# ui_ext_conn.net
KiCad netlist of a schematic drawn in Altium Designer
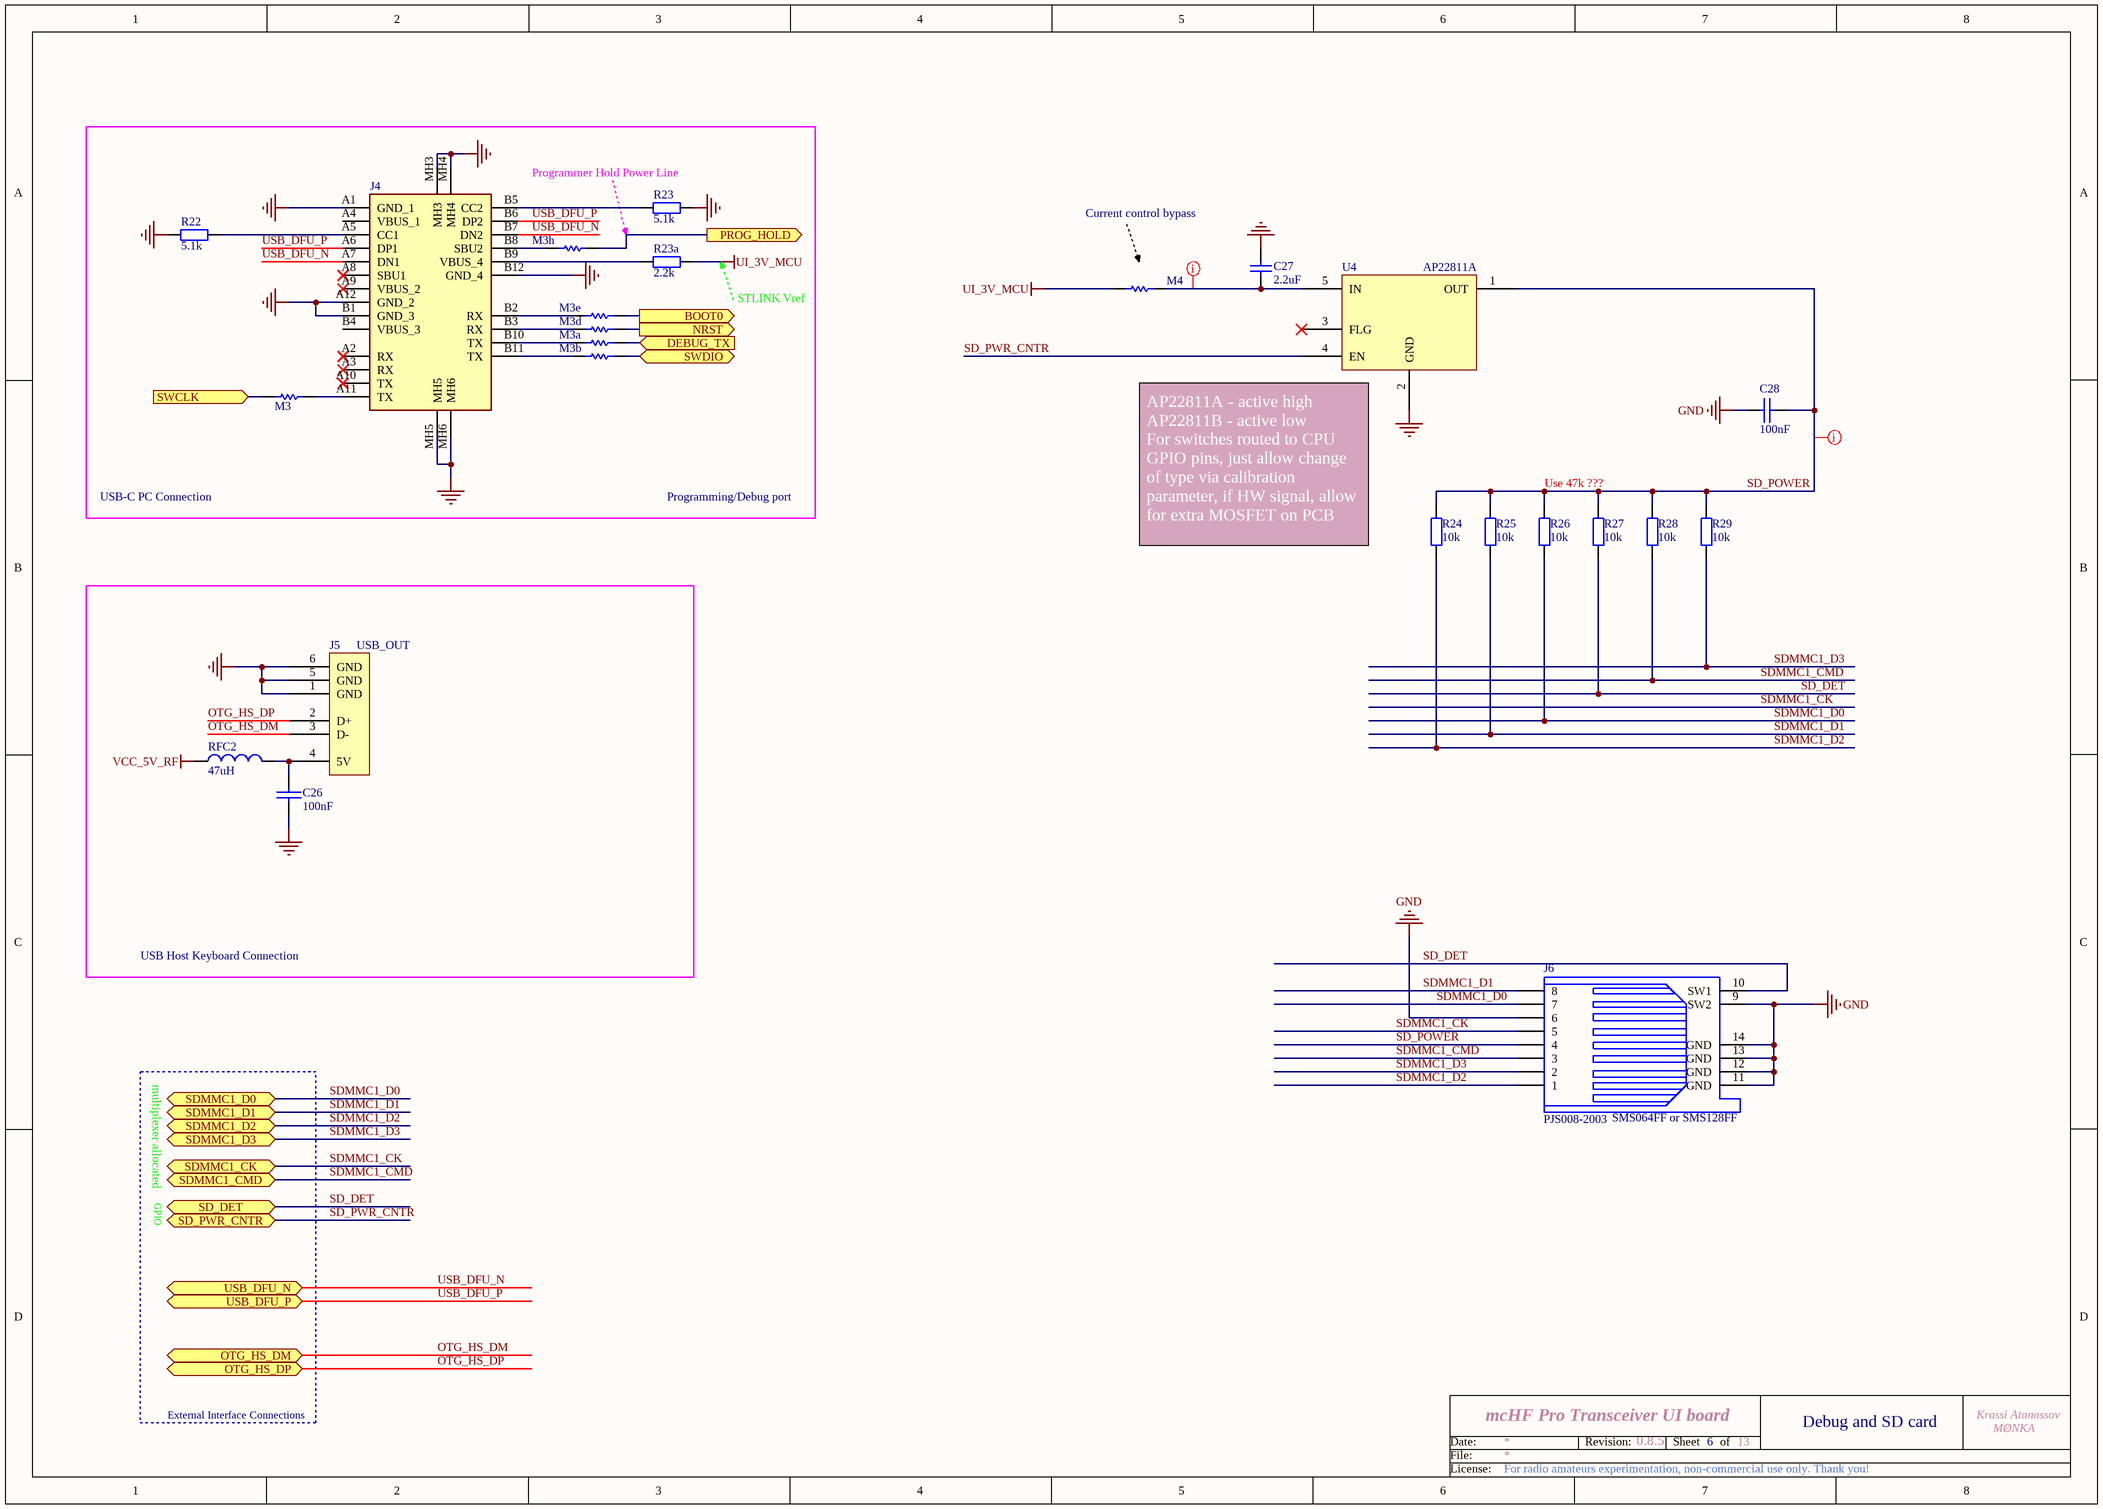
[diagram p0: ui_ext_conn.SchDoc]

(export (version "E")
  (design (tool "Eeschema 10.0.6"))
  (components
    (comp (ref "C26")
      (value "100nF")
      (footprint "0805")
      (description "Capacitor")
      (libsource (lib "mcHF_ui") (part "CAP"))
    )
    (comp (ref "C27")
      (value "2.2uF")
      (footprint "0805")
      (description "0603  X5R 1礔")
      (fields (field (name "TOLERANCE") "10%"))
      (libsource (lib "MB963_1") (part "CAP SMD 0603  X5R 1礔 25V 10%"))
    )
    (comp (ref "C28")
      (value "100nF")
      (footprint "0805")
      (description "Capacitor")
      (libsource (lib "mcHF_ui") (part "CAP"))
    )
    (comp (ref "J4")
      (value "219320-0001")
      (footprint "usbc_24p")
      (fields (field (name "MOUSER PART NUMBER") "538-219320-0001"))
      (libsource (lib "__ui") (part "usbc_24p"))
    )
    (comp (ref "J5")
      (value "USB_OUT")
      (footprint "USB_OUT_A")
      (description "USB Host Connector")
      (libsource (lib "__ui") (part "USB_OUT"))
    )
    (comp (ref "J6")
      (value "PJS008-2003")
      (footprint "PJS008-2003-1")
      (description "Memory Card Connectors MicroSD Card Conn Revrs Mnt Push-Push")
      (libsource (lib "__ui") (part "microSD-PJS008-2003"))
    )
    (comp (ref "M3")
      (value "0")
      (footprint "SB_0603_NO")
      (description "Link")
      (fields (field (name "PUBLISHER") "Altium Limited"))
      (libsource (lib "__ui") (part "Link"))
    )
    (comp (ref "M3a")
      (value "0")
      (footprint "SB_0603_NO")
      (description "Link")
      (fields (field (name "PUBLISHER") "Altium Limited"))
      (libsource (lib "__ui") (part "Link"))
    )
    (comp (ref "M3b")
      (value "0")
      (footprint "SB_0603_NO")
      (description "Link")
      (fields (field (name "PUBLISHER") "Altium Limited"))
      (libsource (lib "__ui") (part "Link"))
    )
    (comp (ref "M3d")
      (value "0")
      (footprint "SB_0603_NO")
      (description "Link")
      (fields (field (name "PUBLISHER") "Altium Limited"))
      (libsource (lib "__ui") (part "Link"))
    )
    (comp (ref "M3e")
      (value "0")
      (footprint "SB_0603_NO")
      (description "Link")
      (fields (field (name "PUBLISHER") "Altium Limited"))
      (libsource (lib "__ui") (part "Link"))
    )
    (comp (ref "M3h")
      (value "0")
      (footprint "SB_0603_NO")
      (description "Link")
      (fields (field (name "PUBLISHER") "Altium Limited"))
      (libsource (lib "__ui") (part "Link"))
    )
    (comp (ref "M4")
      (value "0")
      (footprint "SB_0603")
      (description "Link")
      (fields (field (name "PUBLISHER") "Altium Limited"))
      (libsource (lib "__ui") (part "Link"))
    )
    (comp (ref "R22")
      (value "5.1k")
      (footprint "0805")
      (description "Resistor")
      (libsource (lib "") (part "RES_1"))
    )
    (comp (ref "R23")
      (value "5.1k")
      (footprint "0805")
      (description "Resistor")
      (libsource (lib "") (part "RES_1"))
    )
    (comp (ref "R23a")
      (value "2.2k")
      (footprint "0805")
      (description "Resistor")
      (libsource (lib "") (part "RES_1"))
    )
    (comp (ref "R24")
      (value "10k")
      (footprint "0805")
      (description "Resistor")
      (libsource (lib "mcHF_ui_b") (part "RES"))
    )
    (comp (ref "R25")
      (value "10k")
      (footprint "0805")
      (description "Resistor")
      (libsource (lib "mcHF_ui_b") (part "RES"))
    )
    (comp (ref "R26")
      (value "10k")
      (footprint "0805")
      (description "Resistor")
      (libsource (lib "mcHF_ui_b") (part "RES"))
    )
    (comp (ref "R27")
      (value "10k")
      (footprint "0805")
      (description "Resistor")
      (libsource (lib "mcHF_ui_b") (part "RES"))
    )
    (comp (ref "R28")
      (value "10k")
      (footprint "0805")
      (description "Resistor")
      (libsource (lib "mcHF_ui_b") (part "RES"))
    )
    (comp (ref "R29")
      (value "10k")
      (footprint "0805")
      (description "Resistor")
      (libsource (lib "mcHF_ui_b") (part "RES"))
    )
    (comp (ref "RFC2")
      (value "47uH")
      (footprint "0805")
      (description "Inductor")
      (libsource (lib "mcHF_ui") (part "Inductor"))
    )
    (comp (ref "U4")
      (value "AP22811A")
      (footprint "SOT25-5")
      (description "High-side switch")
      (libsource (lib "__ui") (part "AP22811"))
    )
  )
  (nets
    (net (code "1") (name "/BOOT0") (class "Default")
      (node (ref "M3e") (pin "1") (pinfunction "1_1") (pintype "passive"))
    )
    (net (code "2") (name "/DEBUG_TX") (class "Default")
      (node (ref "M3a") (pin "2") (pinfunction "2_2") (pintype "passive"))
    )
    (net (code "3") (name "/NRST") (class "Default")
      (node (ref "M3d") (pin "2") (pinfunction "2_2") (pintype "passive"))
    )
    (net (code "4") (name "/OTG_HS_DM") (class "Default")
      (node (ref "J5") (pin "3") (pinfunction "D-_3") (pintype "passive"))
    )
    (net (code "5") (name "/OTG_HS_DP") (class "Default")
      (node (ref "J5") (pin "2") (pinfunction "D+_2") (pintype "passive"))
    )
    (net (code "6") (name "/PROG_HOLD") (class "Default")
      (node (ref "M3h") (pin "1") (pinfunction "1_1") (pintype "passive"))
    )
    (net (code "7") (name "/SDMMC1_CK") (class "Default")
      (node (ref "J6") (pin "5") (pinfunction "5_5") (pintype "passive"))
    )
    (net (code "8") (name "/SDMMC1_CMD") (class "Default")
      (node (ref "J6") (pin "3") (pinfunction "3_3") (pintype "passive"))
      (node (ref "R28") (pin "2") (pinfunction "2_2") (pintype "passive"))
    )
    (net (code "9") (name "/SDMMC1_D0") (class "Default")
      (node (ref "J6") (pin "7") (pinfunction "7_7") (pintype "passive"))
      (node (ref "R26") (pin "2") (pinfunction "2_2") (pintype "passive"))
    )
    (net (code "10") (name "/SDMMC1_D1") (class "Default")
      (node (ref "J6") (pin "8") (pinfunction "8_8") (pintype "passive"))
      (node (ref "R25") (pin "2") (pinfunction "2_2") (pintype "passive"))
    )
    (net (code "11") (name "/SDMMC1_D2") (class "Default")
      (node (ref "J6") (pin "1") (pinfunction "1_1") (pintype "passive"))
      (node (ref "R24") (pin "2") (pinfunction "2_2") (pintype "passive"))
    )
    (net (code "12") (name "/SDMMC1_D3") (class "Default")
      (node (ref "J6") (pin "2") (pinfunction "2_2") (pintype "passive"))
      (node (ref "R29") (pin "2") (pinfunction "2_2") (pintype "passive"))
    )
    (net (code "13") (name "/SD_DET") (class "Default")
      (node (ref "J6") (pin "10") (pinfunction "SW1_10") (pintype "passive"))
      (node (ref "R27") (pin "2") (pinfunction "2_2") (pintype "passive"))
    )
    (net (code "14") (name "/SD_POWER") (class "Default")
      (node (ref "C28") (pin "1") (pinfunction "1_1") (pintype "passive"))
      (node (ref "J6") (pin "4") (pinfunction "4_4") (pintype "passive"))
      (node (ref "R24") (pin "1") (pinfunction "1_1") (pintype "passive"))
      (node (ref "R25") (pin "1") (pinfunction "1_1") (pintype "passive"))
      (node (ref "R26") (pin "1") (pinfunction "1_1") (pintype "passive"))
      (node (ref "R27") (pin "1") (pinfunction "1_1") (pintype "passive"))
      (node (ref "R28") (pin "1") (pinfunction "1_1") (pintype "passive"))
      (node (ref "R29") (pin "1") (pinfunction "1_1") (pintype "passive"))
      (node (ref "U4") (pin "1") (pinfunction "OUT_1") (pintype "power_in"))
    )
    (net (code "15") (name "/SD_PWR_CNTR") (class "Default")
      (node (ref "U4") (pin "4") (pinfunction "EN_4") (pintype "passive"))
    )
    (net (code "16") (name "/SWCLK") (class "Default")
      (node (ref "M3") (pin "2") (pinfunction "2_2") (pintype "passive"))
    )
    (net (code "17") (name "/SWDIO") (class "Default")
      (node (ref "M3b") (pin "2") (pinfunction "2_2") (pintype "passive"))
    )
    (net (code "18") (name "/USB_DFU_N") (class "Default")
      (node (ref "J4") (pin "A7") (pinfunction "DN1_A7") (pintype "passive"))
      (node (ref "J4") (pin "B7") (pinfunction "DN2_B7") (pintype "passive"))
    )
    (net (code "19") (name "/USB_DFU_P") (class "Default")
      (node (ref "J4") (pin "A6") (pinfunction "DP1_A6") (pintype "passive"))
      (node (ref "J4") (pin "B6") (pinfunction "DP2_B6") (pintype "passive"))
    )
    (net (code "20") (name "GND") (class "Default")
      (node (ref "C26") (pin "1") (pinfunction "1_1") (pintype "passive"))
      (node (ref "C27") (pin "1") (pinfunction "1_1") (pintype "passive"))
      (node (ref "C28") (pin "2") (pinfunction "2_2") (pintype "passive"))
      (node (ref "J4") (pin "A1") (pinfunction "GND_1_A1") (pintype "passive"))
      (node (ref "J4") (pin "A12") (pinfunction "GND_2_A12") (pintype "passive"))
      (node (ref "J4") (pin "B1") (pinfunction "GND_3_B1") (pintype "passive"))
      (node (ref "J4") (pin "B12") (pinfunction "GND_4_B12") (pintype "passive"))
      (node (ref "J4") (pin "MH3") (pinfunction "MH3_MH3") (pintype "passive"))
      (node (ref "J4") (pin "MH4") (pinfunction "MH4_MH4") (pintype "passive"))
      (node (ref "J4") (pin "MH5") (pinfunction "MH5_MH5") (pintype "passive"))
      (node (ref "J4") (pin "MH6") (pinfunction "MH6_MH6") (pintype "passive"))
      (node (ref "J5") (pin "1") (pinfunction "GND_1") (pintype "passive"))
      (node (ref "J5") (pin "5") (pinfunction "GND_5") (pintype "passive"))
      (node (ref "J5") (pin "6") (pinfunction "GND_6") (pintype "passive"))
      (node (ref "J6") (pin "11") (pinfunction "GND_11") (pintype "passive"))
      (node (ref "J6") (pin "12") (pinfunction "GND_12") (pintype "passive"))
      (node (ref "J6") (pin "13") (pinfunction "GND_13") (pintype "passive"))
      (node (ref "J6") (pin "14") (pinfunction "GND_14") (pintype "passive"))
      (node (ref "J6") (pin "6") (pinfunction "6_6") (pintype "passive"))
      (node (ref "J6") (pin "9") (pinfunction "SW2_9") (pintype "passive"))
      (node (ref "R22") (pin "1") (pinfunction "1_1") (pintype "passive"))
      (node (ref "R23") (pin "2") (pinfunction "2_2") (pintype "passive"))
      (node (ref "U4") (pin "2") (pinfunction "GND_2") (pintype "passive"))
    )
    (net (code "21") (name "Net-(J4-CC1)") (class "Default")
      (node (ref "J4") (pin "A5") (pinfunction "CC1_A5") (pintype "passive"))
      (node (ref "R22") (pin "2") (pinfunction "2_2") (pintype "passive"))
    )
    (net (code "22") (name "Net-(J4-CC2)") (class "Default")
      (node (ref "J4") (pin "B5") (pinfunction "CC2_B5") (pintype "passive"))
      (node (ref "R23") (pin "1") (pinfunction "1_1") (pintype "passive"))
    )
    (net (code "23") (name "Net-(J4-RX-PadB2)") (class "Default")
      (node (ref "J4") (pin "B2") (pinfunction "RX_B2") (pintype "passive"))
      (node (ref "M3e") (pin "2") (pinfunction "2_2") (pintype "passive"))
    )
    (net (code "24") (name "Net-(J4-RX-PadB3)") (class "Default")
      (node (ref "J4") (pin "B3") (pinfunction "RX_B3") (pintype "passive"))
      (node (ref "M3d") (pin "1") (pinfunction "1_1") (pintype "passive"))
    )
    (net (code "25") (name "Net-(J4-SBU2)") (class "Default")
      (node (ref "J4") (pin "B8") (pinfunction "SBU2_B8") (pintype "passive"))
      (node (ref "M3h") (pin "2") (pinfunction "2_2") (pintype "passive"))
    )
    (net (code "26") (name "Net-(J4-TX-PadA11)") (class "Default")
      (node (ref "J4") (pin "A11") (pinfunction "TX_A11") (pintype "passive"))
      (node (ref "M3") (pin "1") (pinfunction "1_1") (pintype "passive"))
    )
    (net (code "27") (name "Net-(J4-TX-PadB10)") (class "Default")
      (node (ref "J4") (pin "B10") (pinfunction "TX_B10") (pintype "passive"))
      (node (ref "M3a") (pin "1") (pinfunction "1_1") (pintype "passive"))
    )
    (net (code "28") (name "Net-(J4-TX-PadB11)") (class "Default")
      (node (ref "J4") (pin "B11") (pinfunction "TX_B11") (pintype "passive"))
      (node (ref "M3b") (pin "1") (pinfunction "1_1") (pintype "passive"))
    )
    (net (code "29") (name "Net-(J4-VBUS_4)") (class "Default")
      (node (ref "J4") (pin "B9") (pinfunction "VBUS_4_B9") (pintype "passive"))
      (node (ref "R23a") (pin "1") (pinfunction "1_1") (pintype "passive"))
    )
    (net (code "30") (name "Net-(J5-5V)") (class "Default")
      (node (ref "C26") (pin "2") (pinfunction "2_2") (pintype "passive"))
      (node (ref "J5") (pin "4") (pinfunction "5V_4") (pintype "passive"))
      (node (ref "RFC2") (pin "2") (pinfunction "2_2") (pintype "passive"))
    )
    (net (code "31") (name "Net-(U4-IN)") (class "Default")
      (node (ref "C27") (pin "2") (pinfunction "2_2") (pintype "passive"))
      (node (ref "M4") (pin "2") (pinfunction "2_2") (pintype "passive"))
      (node (ref "U4") (pin "5") (pinfunction "IN_5") (pintype "power_in"))
    )
    (net (code "32") (name "UI_3V_MCU") (class "Default")
      (node (ref "M4") (pin "1") (pinfunction "1_1") (pintype "passive"))
      (node (ref "R23a") (pin "2") (pinfunction "2_2") (pintype "passive"))
    )
    (net (code "33") (name "VCC_5V_RF") (class "Default")
      (node (ref "RFC2") (pin "1") (pinfunction "1_1") (pintype "passive"))
    )
    (net (code "34") (name "unconnected-(J4-RX-PadA2)") (class "Default")
      (node (ref "J4") (pin "A2") (pinfunction "RX_A2") (pintype "passive+no_connect"))
    )
    (net (code "35") (name "unconnected-(J4-RX-PadA3)") (class "Default")
      (node (ref "J4") (pin "A3") (pinfunction "RX_A3") (pintype "passive+no_connect"))
    )
    (net (code "36") (name "unconnected-(J4-SBU1-PadA8)") (class "Default")
      (node (ref "J4") (pin "A8") (pinfunction "SBU1_A8") (pintype "passive+no_connect"))
    )
    (net (code "37") (name "unconnected-(J4-TX-PadA10)") (class "Default")
      (node (ref "J4") (pin "A10") (pinfunction "TX_A10") (pintype "passive+no_connect"))
    )
    (net (code "38") (name "unconnected-(J4-VBUS_1-PadA4)") (class "Default")
      (node (ref "J4") (pin "A4") (pinfunction "VBUS_1_A4") (pintype "passive"))
    )
    (net (code "39") (name "unconnected-(J4-VBUS_2-PadA9)") (class "Default")
      (node (ref "J4") (pin "A9") (pinfunction "VBUS_2_A9") (pintype "passive+no_connect"))
    )
    (net (code "40") (name "unconnected-(J4-VBUS_3-PadB4)") (class "Default")
      (node (ref "J4") (pin "B4") (pinfunction "VBUS_3_B4") (pintype "passive"))
    )
    (net (code "41") (name "unconnected-(U4-FLG-Pad3)") (class "Default")
      (node (ref "U4") (pin "3") (pinfunction "FLG_3") (pintype "passive+no_connect"))
    )
  )
)
